# Power.net
KiCad netlist of a schematic drawn in Altium Designer
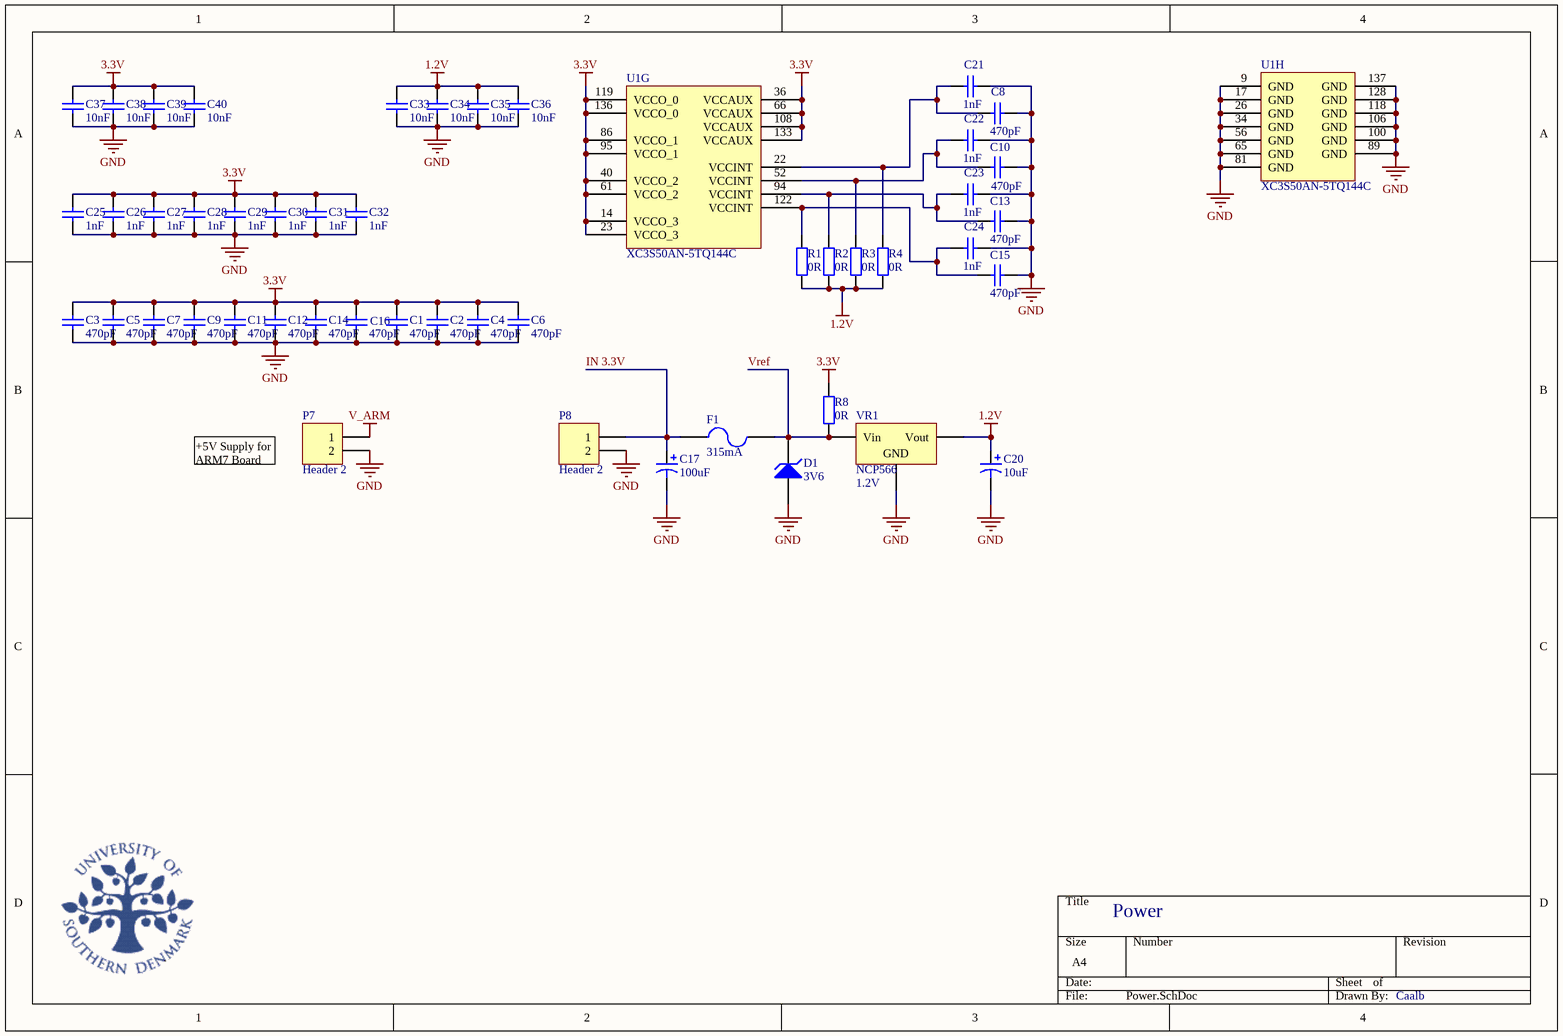
[diagram p0: Power.SchDoc]

(export (version "E")
  (design (tool "Eeschema 10.0.6"))
  (components
    (comp (ref "C1")
      (value "470pF")
      (footprint "0603")
      (description "!Capacitor")
      (fields (field (name "Comment") "Cap") (field (name "PUBLISHER") "Altium Limited"))
      (libsource (lib "") (part "Cap_1"))
    )
    (comp (ref "C2")
      (value "470pF")
      (footprint "0603")
      (description "!Capacitor")
      (fields (field (name "Comment") "Cap") (field (name "PUBLISHER") "Altium Limited"))
      (libsource (lib "") (part "Cap_1"))
    )
    (comp (ref "C3")
      (value "470pF")
      (footprint "0603")
      (description "!Capacitor")
      (fields (field (name "Comment") "Cap") (field (name "PUBLISHER") "Altium Limited"))
      (libsource (lib "") (part "Cap_1"))
    )
    (comp (ref "C4")
      (value "470pF")
      (footprint "0603")
      (description "!Capacitor")
      (fields (field (name "Comment") "Cap") (field (name "PUBLISHER") "Altium Limited"))
      (libsource (lib "") (part "Cap_1"))
    )
    (comp (ref "C5")
      (value "470pF")
      (footprint "0603")
      (description "!Capacitor")
      (fields (field (name "Comment") "Cap") (field (name "PUBLISHER") "Altium Limited"))
      (libsource (lib "") (part "Cap_1"))
    )
    (comp (ref "C6")
      (value "470pF")
      (footprint "0603")
      (description "!Capacitor")
      (fields (field (name "Comment") "Cap") (field (name "PUBLISHER") "Altium Limited"))
      (libsource (lib "") (part "Cap_1"))
    )
    (comp (ref "C7")
      (value "470pF")
      (footprint "0603")
      (description "!Capacitor")
      (fields (field (name "Comment") "Cap") (field (name "PUBLISHER") "Altium Limited"))
      (libsource (lib "") (part "Cap_1"))
    )
    (comp (ref "C8")
      (value "470pF")
      (footprint "0603")
      (description "!Capacitor")
      (fields (field (name "Comment") "Cap") (field (name "PUBLISHER") "Altium Limited"))
      (libsource (lib "") (part "Cap_1"))
    )
    (comp (ref "C9")
      (value "470pF")
      (footprint "0603")
      (description "!Capacitor")
      (fields (field (name "Comment") "Cap") (field (name "PUBLISHER") "Altium Limited"))
      (libsource (lib "") (part "Cap_1"))
    )
    (comp (ref "C10")
      (value "470pF")
      (footprint "0603")
      (description "!Capacitor")
      (fields (field (name "Comment") "Cap") (field (name "PUBLISHER") "Altium Limited"))
      (libsource (lib "") (part "Cap_1"))
    )
    (comp (ref "C11")
      (value "470pF")
      (footprint "0603")
      (description "!Capacitor")
      (fields (field (name "Comment") "Cap") (field (name "PUBLISHER") "Altium Limited"))
      (libsource (lib "") (part "Cap_1"))
    )
    (comp (ref "C12")
      (value "470pF")
      (footprint "0603")
      (description "!Capacitor")
      (fields (field (name "Comment") "Cap") (field (name "PUBLISHER") "Altium Limited"))
      (libsource (lib "") (part "Cap_1"))
    )
    (comp (ref "C13")
      (value "470pF")
      (footprint "0603")
      (description "!Capacitor")
      (fields (field (name "Comment") "Cap") (field (name "PUBLISHER") "Altium Limited"))
      (libsource (lib "") (part "Cap_1"))
    )
    (comp (ref "C14")
      (value "470pF")
      (footprint "0603")
      (description "!Capacitor")
      (fields (field (name "Comment") "Cap") (field (name "PUBLISHER") "Altium Limited"))
      (libsource (lib "") (part "Cap_1"))
    )
    (comp (ref "C15")
      (value "470pF")
      (footprint "0603")
      (description "!Capacitor")
      (fields (field (name "Comment") "Cap") (field (name "PUBLISHER") "Altium Limited"))
      (libsource (lib "") (part "Cap_1"))
    )
    (comp (ref "C16")
      (value "470pF")
      (footprint "0603")
      (description "!Capacitor")
      (fields (field (name "Comment") "Cap") (field (name "PUBLISHER") "Altium Limited"))
      (libsource (lib "") (part "Cap_1"))
    )
    (comp (ref "C17")
      (value "100uF")
      (footprint "Tantal 100uF 10V (lager)")
      (description "!Polarized Capacitor (Radial)")
      (fields (field (name "Comment") "Cap Pol1") (field (name "PUBLISHER") "Altium Limited"))
      (libsource (lib "Miscellaneous Devices") (part "Cap Pol1"))
    )
    (comp (ref "C20")
      (value "10uF")
      (footprint "1206Pol")
      (description "!Polarized Capacitor (Radial)")
      (fields (field (name "Comment") "Cap Pol1") (field (name "PUBLISHER") "Altium Limited"))
      (libsource (lib "Miscellaneous Devices") (part "Cap Pol1"))
    )
    (comp (ref "C21")
      (value "1nF")
      (footprint "0603")
      (description "!Capacitor")
      (fields (field (name "Comment") "Cap") (field (name "PUBLISHER") "Altium Limited"))
      (libsource (lib "") (part "Cap_1"))
    )
    (comp (ref "C22")
      (value "1nF")
      (footprint "0603")
      (description "!Capacitor")
      (fields (field (name "Comment") "Cap") (field (name "PUBLISHER") "Altium Limited"))
      (libsource (lib "") (part "Cap_1"))
    )
    (comp (ref "C23")
      (value "1nF")
      (footprint "0603")
      (description "!Capacitor")
      (fields (field (name "Comment") "Cap") (field (name "PUBLISHER") "Altium Limited"))
      (libsource (lib "") (part "Cap_1"))
    )
    (comp (ref "C24")
      (value "1nF")
      (footprint "0603")
      (description "!Capacitor")
      (fields (field (name "Comment") "Cap") (field (name "PUBLISHER") "Altium Limited"))
      (libsource (lib "") (part "Cap_1"))
    )
    (comp (ref "C25")
      (value "1nF")
      (footprint "0603")
      (description "!Capacitor")
      (fields (field (name "Comment") "Cap") (field (name "PUBLISHER") "Altium Limited"))
      (libsource (lib "Miscellaneous Devices") (part "Cap"))
    )
    (comp (ref "C26")
      (value "1nF")
      (footprint "0603")
      (description "!Capacitor")
      (fields (field (name "Comment") "Cap") (field (name "PUBLISHER") "Altium Limited"))
      (libsource (lib "Miscellaneous Devices") (part "Cap"))
    )
    (comp (ref "C27")
      (value "1nF")
      (footprint "0603")
      (description "!Capacitor")
      (fields (field (name "Comment") "Cap") (field (name "PUBLISHER") "Altium Limited"))
      (libsource (lib "Miscellaneous Devices") (part "Cap"))
    )
    (comp (ref "C28")
      (value "1nF")
      (footprint "0603")
      (description "!Capacitor")
      (fields (field (name "Comment") "Cap") (field (name "PUBLISHER") "Altium Limited"))
      (libsource (lib "Miscellaneous Devices") (part "Cap"))
    )
    (comp (ref "C29")
      (value "1nF")
      (footprint "0603")
      (description "!Capacitor")
      (fields (field (name "Comment") "Cap") (field (name "PUBLISHER") "Altium Limited"))
      (libsource (lib "Miscellaneous Devices") (part "Cap"))
    )
    (comp (ref "C30")
      (value "1nF")
      (footprint "0603")
      (description "!Capacitor")
      (fields (field (name "Comment") "Cap") (field (name "PUBLISHER") "Altium Limited"))
      (libsource (lib "Miscellaneous Devices") (part "Cap"))
    )
    (comp (ref "C31")
      (value "1nF")
      (footprint "0603")
      (description "!Capacitor")
      (fields (field (name "Comment") "Cap") (field (name "PUBLISHER") "Altium Limited"))
      (libsource (lib "Miscellaneous Devices") (part "Cap"))
    )
    (comp (ref "C32")
      (value "1nF")
      (footprint "0603")
      (description "!Capacitor")
      (fields (field (name "Comment") "Cap") (field (name "PUBLISHER") "Altium Limited"))
      (libsource (lib "Miscellaneous Devices") (part "Cap"))
    )
    (comp (ref "C33")
      (value "10nF")
      (footprint "0603")
      (description "!Capacitor")
      (fields (field (name "Comment") "Cap") (field (name "PUBLISHER") "Altium Limited"))
      (libsource (lib "Miscellaneous Devices") (part "Cap"))
    )
    (comp (ref "C34")
      (value "10nF")
      (footprint "0603")
      (description "!Capacitor")
      (fields (field (name "Comment") "Cap") (field (name "PUBLISHER") "Altium Limited"))
      (libsource (lib "Miscellaneous Devices") (part "Cap"))
    )
    (comp (ref "C35")
      (value "10nF")
      (footprint "0603")
      (description "!Capacitor")
      (fields (field (name "Comment") "Cap") (field (name "PUBLISHER") "Altium Limited"))
      (libsource (lib "Miscellaneous Devices") (part "Cap"))
    )
    (comp (ref "C36")
      (value "10nF")
      (footprint "0603")
      (description "!Capacitor")
      (fields (field (name "Comment") "Cap") (field (name "PUBLISHER") "Altium Limited"))
      (libsource (lib "Miscellaneous Devices") (part "Cap"))
    )
    (comp (ref "C37")
      (value "10nF")
      (footprint "1206")
      (description "!Capacitor")
      (fields (field (name "Comment") "Cap") (field (name "PUBLISHER") "Altium Limited"))
      (libsource (lib "Miscellaneous Devices") (part "Cap"))
    )
    (comp (ref "C38")
      (value "10nF")
      (footprint "1206")
      (description "!Capacitor")
      (fields (field (name "Comment") "Cap") (field (name "PUBLISHER") "Altium Limited"))
      (libsource (lib "Miscellaneous Devices") (part "Cap"))
    )
    (comp (ref "C39")
      (value "10nF")
      (footprint "1206")
      (description "!Capacitor")
      (fields (field (name "Comment") "Cap") (field (name "PUBLISHER") "Altium Limited"))
      (libsource (lib "Miscellaneous Devices") (part "Cap"))
    )
    (comp (ref "C40")
      (value "10nF")
      (footprint "1206")
      (description "!Capacitor")
      (fields (field (name "Comment") "Cap") (field (name "PUBLISHER") "Altium Limited"))
      (libsource (lib "Miscellaneous Devices") (part "Cap"))
    )
    (comp (ref "D1")
      (value "3V6")
      (footprint "d1206")
      (description "Zener Diode")
      (fields (field (name "PUBLISHER") "Altium Limited"))
      (libsource (lib "Miscellaneous Devices") (part "D Zener"))
    )
    (comp (ref "F1")
      (value "315mA")
      (footprint "1206")
      (description "Fuse")
      (fields (field (name "PUBLISHER") "Altium Limited"))
      (libsource (lib "Miscellaneous Devices") (part "Fuse 2"))
    )
    (comp (ref "P7")
      (value "Header 2")
      (footprint "HDR2x1 M LÅS")
      (description "Header, 2-Pin M LÅS")
      (fields (field (name "PUBLISHER") "Altium Limited"))
      (libsource (lib "Miscellaneous Connectors") (part "Header 2"))
    )
    (comp (ref "P8")
      (value "Header 2")
      (footprint "HDR2x1 M LÅS")
      (description "Header, 2-Pin M LÅS")
      (fields (field (name "PUBLISHER") "Altium Limited"))
      (libsource (lib "Miscellaneous Connectors") (part "Header 2"))
    )
    (comp (ref "R1")
      (value "0R")
      (footprint "J0805")
      (description "!Resistor")
      (fields (field (name "Comment") "Res2") (field (name "PUBLISHER") "Altium Limited"))
      (libsource (lib "") (part "Res2_1"))
    )
    (comp (ref "R2")
      (value "0R")
      (footprint "J0805")
      (description "!Resistor")
      (fields (field (name "Comment") "Res2") (field (name "PUBLISHER") "Altium Limited"))
      (libsource (lib "") (part "Res2_1"))
    )
    (comp (ref "R3")
      (value "0R")
      (footprint "J0805")
      (description "!Resistor")
      (fields (field (name "Comment") "Res2") (field (name "PUBLISHER") "Altium Limited"))
      (libsource (lib "") (part "Res2_1"))
    )
    (comp (ref "R4")
      (value "0R")
      (footprint "J0805")
      (description "!Resistor")
      (fields (field (name "Comment") "Res2") (field (name "PUBLISHER") "Altium Limited"))
      (libsource (lib "") (part "Res2_1"))
    )
    (comp (ref "R8")
      (value "0R")
      (footprint "J0805")
      (description "!Resistor")
      (fields (field (name "Comment") "Res2") (field (name "PUBLISHER") "Altium Limited"))
      (libsource (lib "Miscellaneous Devices") (part "Res2"))
    )
    (comp (ref "U1")
      (value "XC3S50AN-5TQ144C")
      (footprint "TQ144_L")
      (description "Spartan-3AN Non-Volatile FPGA, 108 User I/Os, 144-Pin TQFP, High Performance, Commercial Grade")
      (fields (field (name "PUBLISHER") "Altium Limited"))
      (libsource (lib "Xilinx Spartan-3AN") (part "XC3S50AN-5TQ144C"))
    )
    (comp (ref "VR1")
      (value "NCP566")
      (footprint "SOT-223")
      (description "Volt Reg NCP566")
      (fields (field (name "ALTIUM_VALUE") "1.2V") (field (name "PUBLISHER") "Altium Limited"))
      (libsource (lib "Miscellaneous Devices") (part "Volt Reg"))
    )
  )
  (nets
    (net (code "1") (name "/IN 3.3V") (class "Default")
      (node (ref "C17") (pin "1") (pinfunction "1_1") (pintype "passive"))
      (node (ref "F1") (pin "1") (pinfunction "1_1") (pintype "passive"))
      (node (ref "P8") (pin "1") (pinfunction "1_1") (pintype "passive"))
    )
    (net (code "2") (name "/Vref") (class "Default")
      (node (ref "D1") (pin "2") (pinfunction "K_2") (pintype "passive"))
      (node (ref "F1") (pin "2") (pinfunction "2_2") (pintype "passive"))
      (node (ref "R8") (pin "2") (pinfunction "2_2") (pintype "passive"))
      (node (ref "VR1") (pin "1") (pinfunction "Vin_1") (pintype "passive"))
    )
    (net (code "3") (name "1.2V") (class "Default")
      (node (ref "C20") (pin "1") (pinfunction "1_1") (pintype "passive"))
      (node (ref "C33") (pin "2") (pinfunction "2_2") (pintype "passive"))
      (node (ref "C34") (pin "2") (pinfunction "2_2") (pintype "passive"))
      (node (ref "C35") (pin "2") (pinfunction "2_2") (pintype "passive"))
      (node (ref "C36") (pin "2") (pinfunction "2_2") (pintype "passive"))
      (node (ref "R1") (pin "1") (pinfunction "1_1") (pintype "passive"))
      (node (ref "R2") (pin "1") (pinfunction "1_1") (pintype "passive"))
      (node (ref "R3") (pin "1") (pinfunction "1_1") (pintype "passive"))
      (node (ref "R4") (pin "1") (pinfunction "1_1") (pintype "passive"))
      (node (ref "VR1") (pin "3") (pinfunction "Vout_3") (pintype "passive"))
    )
    (net (code "4") (name "3.3V") (class "Default")
      (node (ref "C1") (pin "1") (pinfunction "1_1") (pintype "passive"))
      (node (ref "C11") (pin "2") (pinfunction "2_2") (pintype "passive"))
      (node (ref "C12") (pin "2") (pinfunction "2_2") (pintype "passive"))
      (node (ref "C14") (pin "2") (pinfunction "2_2") (pintype "passive"))
      (node (ref "C16") (pin "2") (pinfunction "2_2") (pintype "passive"))
      (node (ref "C2") (pin "1") (pinfunction "1_1") (pintype "passive"))
      (node (ref "C25") (pin "2") (pinfunction "2_2") (pintype "passive"))
      (node (ref "C26") (pin "2") (pinfunction "2_2") (pintype "passive"))
      (node (ref "C27") (pin "2") (pinfunction "2_2") (pintype "passive"))
      (node (ref "C28") (pin "2") (pinfunction "2_2") (pintype "passive"))
      (node (ref "C29") (pin "2") (pinfunction "2_2") (pintype "passive"))
      (node (ref "C3") (pin "2") (pinfunction "2_2") (pintype "passive"))
      (node (ref "C30") (pin "2") (pinfunction "2_2") (pintype "passive"))
      (node (ref "C31") (pin "2") (pinfunction "2_2") (pintype "passive"))
      (node (ref "C32") (pin "2") (pinfunction "2_2") (pintype "passive"))
      (node (ref "C37") (pin "2") (pinfunction "2_2") (pintype "passive"))
      (node (ref "C38") (pin "2") (pinfunction "2_2") (pintype "passive"))
      (node (ref "C39") (pin "2") (pinfunction "2_2") (pintype "passive"))
      (node (ref "C4") (pin "1") (pinfunction "1_1") (pintype "passive"))
      (node (ref "C40") (pin "2") (pinfunction "2_2") (pintype "passive"))
      (node (ref "C5") (pin "2") (pinfunction "2_2") (pintype "passive"))
      (node (ref "C6") (pin "1") (pinfunction "1_1") (pintype "passive"))
      (node (ref "C7") (pin "2") (pinfunction "2_2") (pintype "passive"))
      (node (ref "C9") (pin "2") (pinfunction "2_2") (pintype "passive"))
      (node (ref "R8") (pin "1") (pinfunction "1_1") (pintype "passive"))
      (node (ref "U1") (pin "108") (pinfunction "VCCAUX_108") (pintype "power_in"))
      (node (ref "U1") (pin "119") (pinfunction "VCCO_0_119") (pintype "power_in"))
      (node (ref "U1") (pin "133") (pinfunction "VCCAUX_133") (pintype "power_in"))
      (node (ref "U1") (pin "136") (pinfunction "VCCO_0_136") (pintype "power_in"))
      (node (ref "U1") (pin "14") (pinfunction "VCCO_3_14") (pintype "power_in"))
      (node (ref "U1") (pin "23") (pinfunction "VCCO_3_23") (pintype "power_in"))
      (node (ref "U1") (pin "36") (pinfunction "VCCAUX_36") (pintype "power_in"))
      (node (ref "U1") (pin "40") (pinfunction "VCCO_2_40") (pintype "power_in"))
      (node (ref "U1") (pin "61") (pinfunction "VCCO_2_61") (pintype "power_in"))
      (node (ref "U1") (pin "66") (pinfunction "VCCAUX_66") (pintype "power_in"))
      (node (ref "U1") (pin "86") (pinfunction "VCCO_1_86") (pintype "power_in"))
      (node (ref "U1") (pin "95") (pinfunction "VCCO_1_95") (pintype "power_in"))
    )
    (net (code "5") (name "GND") (class "Default")
      (node (ref "C1") (pin "2") (pinfunction "2_2") (pintype "passive"))
      (node (ref "C10") (pin "2") (pinfunction "2_2") (pintype "passive"))
      (node (ref "C11") (pin "1") (pinfunction "1_1") (pintype "passive"))
      (node (ref "C12") (pin "1") (pinfunction "1_1") (pintype "passive"))
      (node (ref "C13") (pin "2") (pinfunction "2_2") (pintype "passive"))
      (node (ref "C14") (pin "1") (pinfunction "1_1") (pintype "passive"))
      (node (ref "C15") (pin "2") (pinfunction "2_2") (pintype "passive"))
      (node (ref "C16") (pin "1") (pinfunction "1_1") (pintype "passive"))
      (node (ref "C17") (pin "2") (pinfunction "2_2") (pintype "passive"))
      (node (ref "C2") (pin "2") (pinfunction "2_2") (pintype "passive"))
      (node (ref "C20") (pin "2") (pinfunction "2_2") (pintype "passive"))
      (node (ref "C21") (pin "2") (pinfunction "2_2") (pintype "passive"))
      (node (ref "C22") (pin "2") (pinfunction "2_2") (pintype "passive"))
      (node (ref "C23") (pin "2") (pinfunction "2_2") (pintype "passive"))
      (node (ref "C24") (pin "2") (pinfunction "2_2") (pintype "passive"))
      (node (ref "C25") (pin "1") (pinfunction "1_1") (pintype "passive"))
      (node (ref "C26") (pin "1") (pinfunction "1_1") (pintype "passive"))
      (node (ref "C27") (pin "1") (pinfunction "1_1") (pintype "passive"))
      (node (ref "C28") (pin "1") (pinfunction "1_1") (pintype "passive"))
      (node (ref "C29") (pin "1") (pinfunction "1_1") (pintype "passive"))
      (node (ref "C3") (pin "1") (pinfunction "1_1") (pintype "passive"))
      (node (ref "C30") (pin "1") (pinfunction "1_1") (pintype "passive"))
      (node (ref "C31") (pin "1") (pinfunction "1_1") (pintype "passive"))
      (node (ref "C32") (pin "1") (pinfunction "1_1") (pintype "passive"))
      (node (ref "C33") (pin "1") (pinfunction "1_1") (pintype "passive"))
      (node (ref "C34") (pin "1") (pinfunction "1_1") (pintype "passive"))
      (node (ref "C35") (pin "1") (pinfunction "1_1") (pintype "passive"))
      (node (ref "C36") (pin "1") (pinfunction "1_1") (pintype "passive"))
      (node (ref "C37") (pin "1") (pinfunction "1_1") (pintype "passive"))
      (node (ref "C38") (pin "1") (pinfunction "1_1") (pintype "passive"))
      (node (ref "C39") (pin "1") (pinfunction "1_1") (pintype "passive"))
      (node (ref "C4") (pin "2") (pinfunction "2_2") (pintype "passive"))
      (node (ref "C40") (pin "1") (pinfunction "1_1") (pintype "passive"))
      (node (ref "C5") (pin "1") (pinfunction "1_1") (pintype "passive"))
      (node (ref "C6") (pin "2") (pinfunction "2_2") (pintype "passive"))
      (node (ref "C7") (pin "1") (pinfunction "1_1") (pintype "passive"))
      (node (ref "C8") (pin "2") (pinfunction "2_2") (pintype "passive"))
      (node (ref "C9") (pin "1") (pinfunction "1_1") (pintype "passive"))
      (node (ref "D1") (pin "1") (pinfunction "A_1") (pintype "passive"))
      (node (ref "P7") (pin "2") (pinfunction "2_2") (pintype "passive"))
      (node (ref "P8") (pin "2") (pinfunction "2_2") (pintype "passive"))
      (node (ref "U1") (pin "100") (pinfunction "GND_100") (pintype "power_in"))
      (node (ref "U1") (pin "106") (pinfunction "GND_106") (pintype "power_in"))
      (node (ref "U1") (pin "118") (pinfunction "GND_118") (pintype "power_in"))
      (node (ref "U1") (pin "128") (pinfunction "GND_128") (pintype "power_in"))
      (node (ref "U1") (pin "137") (pinfunction "GND_137") (pintype "power_in"))
      (node (ref "U1") (pin "17") (pinfunction "GND_17") (pintype "power_in"))
      (node (ref "U1") (pin "26") (pinfunction "GND_26") (pintype "power_in"))
      (node (ref "U1") (pin "34") (pinfunction "GND_34") (pintype "power_in"))
      (node (ref "U1") (pin "56") (pinfunction "GND_56") (pintype "power_in"))
      (node (ref "U1") (pin "65") (pinfunction "GND_65") (pintype "power_in"))
      (node (ref "U1") (pin "81") (pinfunction "GND_81") (pintype "power_in"))
      (node (ref "U1") (pin "89") (pinfunction "GND_89") (pintype "power_in"))
      (node (ref "U1") (pin "9") (pinfunction "GND_9") (pintype "power_in"))
      (node (ref "VR1") (pin "2") (pinfunction "GND_2") (pintype "passive"))
    )
    (net (code "6") (name "Net-(C10-Pad1)") (class "Default")
      (node (ref "C10") (pin "1") (pinfunction "1_1") (pintype "passive"))
      (node (ref "C22") (pin "1") (pinfunction "1_1") (pintype "passive"))
      (node (ref "R3") (pin "2") (pinfunction "2_2") (pintype "passive"))
      (node (ref "U1") (pin "52") (pinfunction "VCCINT_52") (pintype "power_in"))
    )
    (net (code "7") (name "Net-(C13-Pad1)") (class "Default")
      (node (ref "C13") (pin "1") (pinfunction "1_1") (pintype "passive"))
      (node (ref "C23") (pin "1") (pinfunction "1_1") (pintype "passive"))
      (node (ref "R2") (pin "2") (pinfunction "2_2") (pintype "passive"))
      (node (ref "U1") (pin "94") (pinfunction "VCCINT_94") (pintype "power_in"))
    )
    (net (code "8") (name "Net-(C15-Pad1)") (class "Default")
      (node (ref "C15") (pin "1") (pinfunction "1_1") (pintype "passive"))
      (node (ref "C24") (pin "1") (pinfunction "1_1") (pintype "passive"))
      (node (ref "R1") (pin "2") (pinfunction "2_2") (pintype "passive"))
      (node (ref "U1") (pin "122") (pinfunction "VCCINT_122") (pintype "power_in"))
    )
    (net (code "9") (name "Net-(C21-Pad1)") (class "Default")
      (node (ref "C21") (pin "1") (pinfunction "1_1") (pintype "passive"))
      (node (ref "C8") (pin "1") (pinfunction "1_1") (pintype "passive"))
      (node (ref "R4") (pin "2") (pinfunction "2_2") (pintype "passive"))
      (node (ref "U1") (pin "22") (pinfunction "VCCINT_22") (pintype "power_in"))
    )
    (net (code "10") (name "V_ARM") (class "Default")
      (node (ref "P7") (pin "1") (pinfunction "1_1") (pintype "passive"))
    )
  )
)
